# adc_mcp3913.net
KiCad netlist of a schematic drawn in Altium Designer
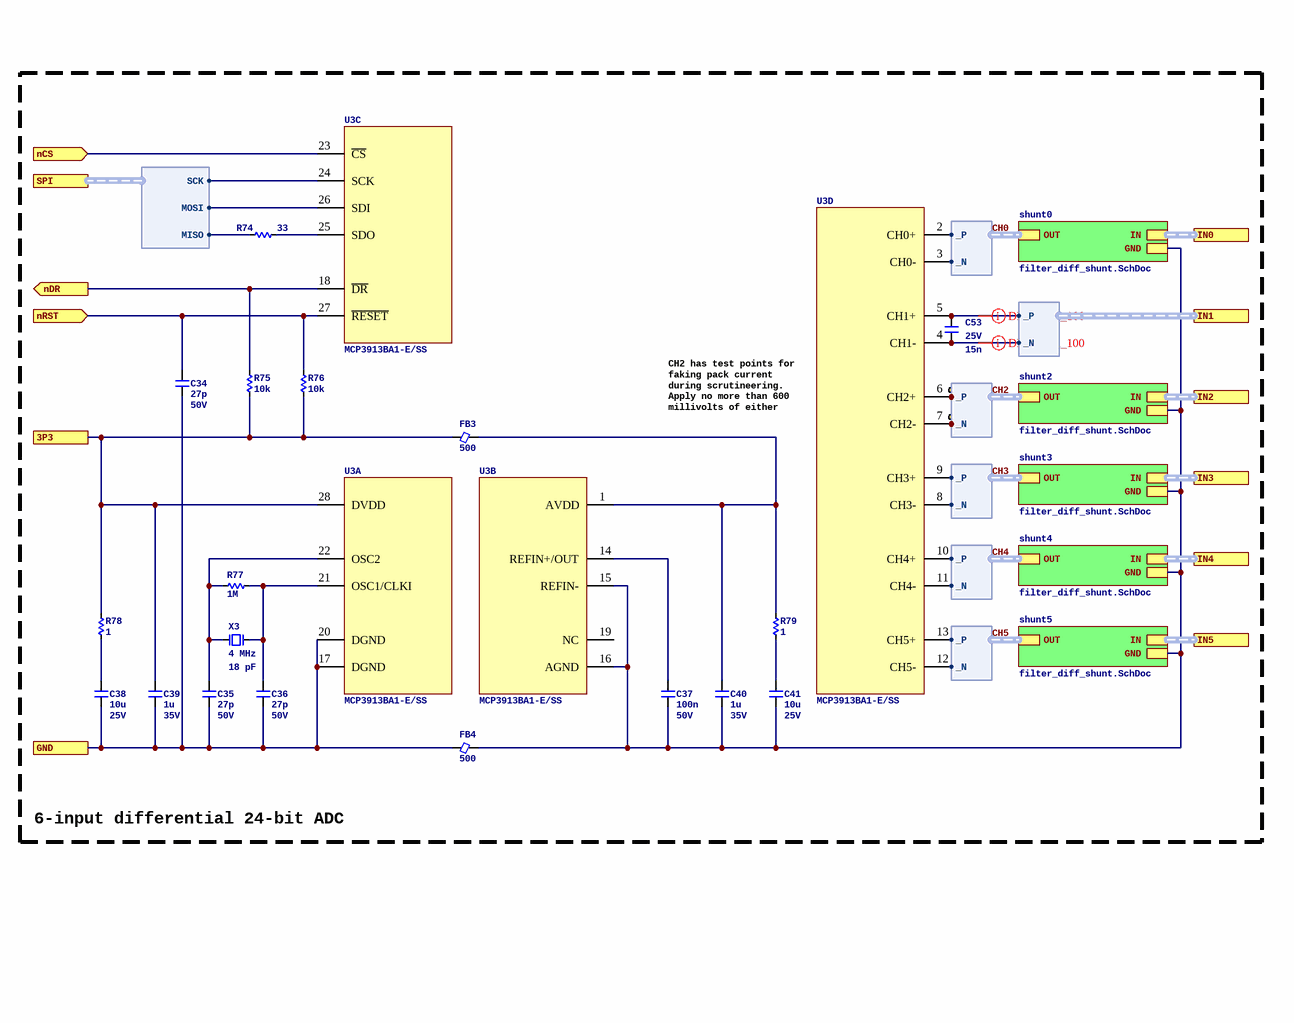
[diagram p0: adc_mcp3913.SchDoc]

(export (version "E")
  (design (tool "Eeschema 10.0.6"))
  (components
    (comp (ref "C34")
      (value "0402CG270J500NT")
      (footprint "C0402")
      (fields
        (field (name "CAPACITANCE") "27p")
        (field (name "MANUFACTURER") "FH(Guangdong Fenghua Advanced Tech)")
        (field (name "VOLTAGE RATING") "50V")
      )
      (libsource (lib "database") (part "__template_cap"))
    )
    (comp (ref "C35")
      (value "0402CG270J500NT")
      (footprint "C0402")
      (fields
        (field (name "CAPACITANCE") "27p")
        (field (name "MANUFACTURER") "FH(Guangdong Fenghua Advanced Tech)")
        (field (name "VOLTAGE RATING") "50V")
      )
      (libsource (lib "database") (part "__template_cap"))
    )
    (comp (ref "C36")
      (value "0402CG270J500NT")
      (footprint "C0402")
      (fields
        (field (name "CAPACITANCE") "27p")
        (field (name "MANUFACTURER") "FH(Guangdong Fenghua Advanced Tech)")
        (field (name "VOLTAGE RATING") "50V")
      )
      (libsource (lib "database") (part "__template_cap"))
    )
    (comp (ref "C37")
      (value "CL05B104KB54PNC")
      (footprint "C0402")
      (fields
        (field (name "CAPACITANCE") "100n")
        (field (name "MANUFACTURER") "Samsung Electro-Mechanics")
        (field (name "VOLTAGE RATING") "50V")
      )
      (libsource (lib "database") (part "__template_cap"))
    )
    (comp (ref "C38")
      (value "CL21B106KAYQNNE")
      (footprint "C0805")
      (fields
        (field (name "CAPACITANCE") "10u")
        (field (name "MANUFACTURER") "Samsung Electro-Mechanics")
        (field (name "VOLTAGE RATING") "25V")
      )
      (libsource (lib "database") (part "__template_cap"))
    )
    (comp (ref "C39")
      (value "GMK107AB7105KAHT")
      (footprint "C0603")
      (fields
        (field (name "CAPACITANCE") "1u")
        (field (name "MANUFACTURER") "Taiyo Yuden")
        (field (name "VOLTAGE RATING") "35V")
      )
      (libsource (lib "database") (part "__template_cap"))
    )
    (comp (ref "C40")
      (value "GMK107AB7105KAHT")
      (footprint "C0603")
      (fields
        (field (name "CAPACITANCE") "1u")
        (field (name "MANUFACTURER") "Taiyo Yuden")
        (field (name "VOLTAGE RATING") "35V")
      )
      (libsource (lib "database") (part "__template_cap"))
    )
    (comp (ref "C41")
      (value "CL21B106KAYQNNE")
      (footprint "C0805")
      (fields
        (field (name "CAPACITANCE") "10u")
        (field (name "MANUFACTURER") "Samsung Electro-Mechanics")
        (field (name "VOLTAGE RATING") "25V")
      )
      (libsource (lib "database") (part "__template_cap"))
    )
    (comp (ref "C53")
      (value "0402B153K250NT")
      (footprint "C0402")
      (fields
        (field (name "VOLTAGE RATING") "25V")
        (field (name "CAPACITANCE") "15n")
        (field (name "MANUFACTURER") "FH(Guangdong Fenghua Advanced Tech)")
      )
      (libsource (lib "database") (part "__template_cap"))
    )
    (comp (ref "FB3")
      (value "BLM15AX601SN1D")
      (footprint "FB0402")
      (fields (field (name "MANUFACTURER") "Murata Electronics") (field (name "CURRENT RATING (MA)") "500"))
      (libsource (lib "database") (part "__template_fb"))
    )
    (comp (ref "FB4")
      (value "BLM15AX601SN1D")
      (footprint "FB0402")
      (fields (field (name "MANUFACTURER") "Murata Electronics") (field (name "CURRENT RATING (MA)") "500"))
      (libsource (lib "database") (part "__template_fb"))
    )
    (comp (ref "R74")
      (value "33")
      (footprint "R0402")
      (fields
        (field (name "TOLERANCE") "1%")
        (field (name "MANUFACTURER PART NUMBER") "0402WGF330JTCE")
        (field (name "MANUFACTURER") "UNI-ROYAL(Uniroyal Elec)")
      )
      (libsource (lib "database") (part "__template_resistor"))
    )
    (comp (ref "R75")
      (value "10k")
      (footprint "R0402")
      (fields
        (field (name "TOLERANCE") "1%")
        (field (name "MANUFACTURER PART NUMBER") "0402WGF1002TCE")
        (field (name "MANUFACTURER") "UNI-ROYAL(Uniroyal Elec)")
      )
      (libsource (lib "database") (part "__template_resistor"))
    )
    (comp (ref "R76")
      (value "10k")
      (footprint "R0402")
      (fields
        (field (name "TOLERANCE") "1%")
        (field (name "MANUFACTURER PART NUMBER") "0402WGF1002TCE")
        (field (name "MANUFACTURER") "UNI-ROYAL(Uniroyal Elec)")
      )
      (libsource (lib "database") (part "__template_resistor"))
    )
    (comp (ref "R77")
      (value "1M")
      (footprint "R0402")
      (fields
        (field (name "TOLERANCE") "1%")
        (field (name "MANUFACTURER PART NUMBER") "0402WGF1004TCE")
        (field (name "MANUFACTURER") "UNI-ROYAL(Uniroyal Elec)")
      )
      (libsource (lib "database") (part "__template_resistor"))
    )
    (comp (ref "R78")
      (value "1")
      (footprint "R0402")
      (fields
        (field (name "TOLERANCE") "1%")
        (field (name "MANUFACTURER PART NUMBER") "CRCW04021R00FKED")
        (field (name "MANUFACTURER") "Vishay Intertech")
      )
      (libsource (lib "database") (part "__template_resistor"))
    )
    (comp (ref "R79")
      (value "1")
      (footprint "R0402")
      (fields
        (field (name "TOLERANCE") "1%")
        (field (name "MANUFACTURER PART NUMBER") "CRCW04021R00FKED")
        (field (name "MANUFACTURER") "Vishay Intertech")
      )
      (libsource (lib "database") (part "__template_resistor"))
    )
    (comp (ref "TP71")
      (value "RH-5000")
      (footprint "TP_RH-5000")
      (fields (field (name "MANUFACTURER") "ronghe"))
      (libsource (lib "database") (part "__template_testpoint"))
    )
    (comp (ref "TP72")
      (value "RH-5001")
      (footprint "TP_RH-5001")
      (fields (field (name "MANUFACTURER") "ronghe"))
      (libsource (lib "database") (part "__template_testpoint"))
    )
    (comp (ref "U3")
      (value "MCP3913BA1-E/SS")
      (footprint "28SSOP65")
      (description "6 Channel AFE 16, 24 Bit 28-SSOP")
      (fields (field (name "MANUFACTURER") "Microchip"))
      (libsource (lib "") (part "ADC_MCP3913BA1-E/SS_1"))
    )
    (comp (ref "X3")
      (value "ABLS2-4.000MHZ-D4Y-T")
      (footprint "XTAL_HC49US_SMD")
      (description "CRYSTAL 4.000 MHZ 18PF SMD")
      (fields
        (field (name "MANUFACTURER") "Abracon LLC")
        (field (name "FREQUENCY") "4 MHz")
        (field (name "LOAD CAPACITANCE") "18 pF")
      )
      (libsource (lib "SSCP") (part "XTAL_ABLS2-4.000MHZ-D4Y-T"))
    )
  )
  (nets
    (net (code "13") (name "/3P3") (class "Default")
      (node (ref "C39") (pin "1") (pintype "passive"))
      (node (ref "FB3") (pin "1") (pintype "passive"))
      (node (ref "R75") (pin "2") (pintype "passive"))
      (node (ref "R76") (pin "2") (pintype "passive"))
      (node (ref "R78") (pin "2") (pintype "passive"))
      (node (ref "U3") (pin "28") (pinfunction "DVDD_28") (pintype "passive"))
    )
    (net (code "19") (name "/GND") (class "Default")
      (node (ref "C34") (pin "2") (pintype "passive"))
      (node (ref "C35") (pin "2") (pintype "passive"))
      (node (ref "C36") (pin "2") (pintype "passive"))
      (node (ref "C38") (pin "2") (pintype "passive"))
      (node (ref "C39") (pin "2") (pintype "passive"))
      (node (ref "FB4") (pin "1") (pintype "passive"))
      (node (ref "U3") (pin "17") (pinfunction "DGND_17") (pintype "passive"))
      (node (ref "U3") (pin "20") (pinfunction "DGND_20") (pintype "passive"))
    )
    (net (code "20") (name "/GND_1") (class "Default")
      (node (ref "C37") (pin "2") (pintype "passive"))
      (node (ref "C40") (pin "2") (pintype "passive"))
      (node (ref "C41") (pin "2") (pintype "passive"))
      (node (ref "FB4") (pin "2") (pintype "passive"))
      (node (ref "U3") (pin "15") (pinfunction "REFIN-_15") (pintype "passive"))
      (node (ref "U3") (pin "16") (pinfunction "AGND_16") (pintype "passive"))
    )
    (net (code "26") (name "/MISO") (class "Default") (node (ref "R74") (pin "2") (pintype "passive")))
    (net (code "27") (name "/MOSI") (class "Default")
      (node (ref "U3") (pin "26") (pinfunction "SDI_26") (pintype "passive"))
    )
    (net (code "28") (name "/SCK") (class "Default")
      (node (ref "U3") (pin "24") (pinfunction "SCK_24") (pintype "passive"))
    )
    (net (code "29") (name "/nCS") (class "Default")
      (node (ref "U3") (pin "23") (pinfunction "~{CS}_23") (pintype "passive"))
    )
    (net (code "30") (name "/nDR") (class "Default")
      (node (ref "R75") (pin "1") (pintype "passive"))
      (node (ref "U3") (pin "18") (pinfunction "~{DR}_18") (pintype "passive"))
    )
    (net (code "31") (name "/nRST") (class "Default")
      (node (ref "C34") (pin "1") (pintype "passive"))
      (node (ref "R76") (pin "1") (pintype "passive"))
      (node (ref "U3") (pin "27") (pinfunction "~{RESET}_27") (pintype "passive"))
    )
    (net (code "34") (name "Net-(C38-Pad1)") (class "Default")
      (node (ref "C38") (pin "1") (pintype "passive"))
      (node (ref "R78") (pin "1") (pintype "passive"))
    )
    (net (code "35") (name "Net-(C41-Pad1)") (class "Default")
      (node (ref "C41") (pin "1") (pintype "passive"))
      (node (ref "R79") (pin "1") (pintype "passive"))
    )
    (net (code "36") (name "Net-(U3A-OSC1{slash}CLKI)") (class "Default")
      (node (ref "C36") (pin "1") (pintype "passive"))
      (node (ref "R77") (pin "1") (pintype "passive"))
      (node (ref "U3") (pin "21") (pinfunction "OSC1/CLKI_21") (pintype "passive"))
      (node (ref "X3") (pin "1") (pinfunction "1_1") (pintype "passive"))
    )
    (net (code "37") (name "Net-(U3A-OSC2)") (class "Default")
      (node (ref "C35") (pin "1") (pintype "passive"))
      (node (ref "R77") (pin "2") (pintype "passive"))
      (node (ref "U3") (pin "22") (pinfunction "OSC2_22") (pintype "passive"))
      (node (ref "X3") (pin "2") (pinfunction "2_2") (pintype "passive"))
    )
    (net (code "38") (name "Net-(U3B-AVDD)") (class "Default")
      (node (ref "C40") (pin "1") (pintype "passive"))
      (node (ref "FB3") (pin "2") (pintype "passive"))
      (node (ref "R79") (pin "2") (pintype "passive"))
      (node (ref "U3") (pin "1") (pinfunction "AVDD_1") (pintype "passive"))
    )
    (net (code "39") (name "Net-(U3B-REFIN+{slash}OUT)") (class "Default")
      (node (ref "C37") (pin "1") (pintype "passive"))
      (node (ref "U3") (pin "14") (pinfunction "REFIN+/OUT_14") (pintype "passive"))
    )
    (net (code "40") (name "Net-(U3C-SDO)") (class "Default")
      (node (ref "R74") (pin "1") (pintype "passive"))
      (node (ref "U3") (pin "25") (pinfunction "SDO_25") (pintype "passive"))
    )
    (net (code "41") (name "Net-(U3D-CH1+)") (class "Default")
      (node (ref "C53") (pin "1") (pintype "passive"))
      (node (ref "U3") (pin "5") (pinfunction "CH1+_5") (pintype "passive"))
    )
    (net (code "42") (name "Net-(U3D-CH1-)") (class "Default")
      (node (ref "C53") (pin "2") (pintype "passive"))
      (node (ref "U3") (pin "4") (pinfunction "CH1-_4") (pintype "passive"))
    )
    (net (code "43") (name "Net-(U3D-CH2+)") (class "Default")
      (node (ref "TP71") (pin "1") (pintype "passive"))
      (node (ref "U3") (pin "6") (pinfunction "CH2+_6") (pintype "passive"))
    )
    (net (code "44") (name "Net-(U3D-CH2-)") (class "Default")
      (node (ref "TP72") (pin "1") (pintype "passive"))
      (node (ref "U3") (pin "7") (pinfunction "CH2-_7") (pintype "passive"))
    )
    (net (code "45") (name "unconnected-(U3B-NC-Pad19)") (class "Default")
      (node (ref "U3") (pin "19") (pinfunction "NC_19") (pintype "passive"))
    )
    (net (code "46") (name "unconnected-(U3D-CH0+-Pad2)") (class "Default")
      (node (ref "U3") (pin "2") (pinfunction "CH0+_2") (pintype "passive"))
    )
    (net (code "47") (name "unconnected-(U3D-CH0--Pad3)") (class "Default")
      (node (ref "U3") (pin "3") (pinfunction "CH0-_3") (pintype "passive"))
    )
    (net (code "48") (name "unconnected-(U3D-CH3+-Pad9)") (class "Default")
      (node (ref "U3") (pin "9") (pinfunction "CH3+_9") (pintype "passive"))
    )
    (net (code "49") (name "unconnected-(U3D-CH3--Pad8)") (class "Default")
      (node (ref "U3") (pin "8") (pinfunction "CH3-_8") (pintype "passive"))
    )
    (net (code "50") (name "unconnected-(U3D-CH4+-Pad10)") (class "Default")
      (node (ref "U3") (pin "10") (pinfunction "CH4+_10") (pintype "passive"))
    )
    (net (code "51") (name "unconnected-(U3D-CH4--Pad11)") (class "Default")
      (node (ref "U3") (pin "11") (pinfunction "CH4-_11") (pintype "passive"))
    )
    (net (code "52") (name "unconnected-(U3D-CH5+-Pad13)") (class "Default")
      (node (ref "U3") (pin "13") (pinfunction "CH5+_13") (pintype "passive"))
    )
    (net (code "53") (name "unconnected-(U3D-CH5--Pad12)") (class "Default")
      (node (ref "U3") (pin "12") (pinfunction "CH5-_12") (pintype "passive"))
    )
  )
)
